# Analog_Master.net
KiCad netlist of a schematic drawn in EAGLE
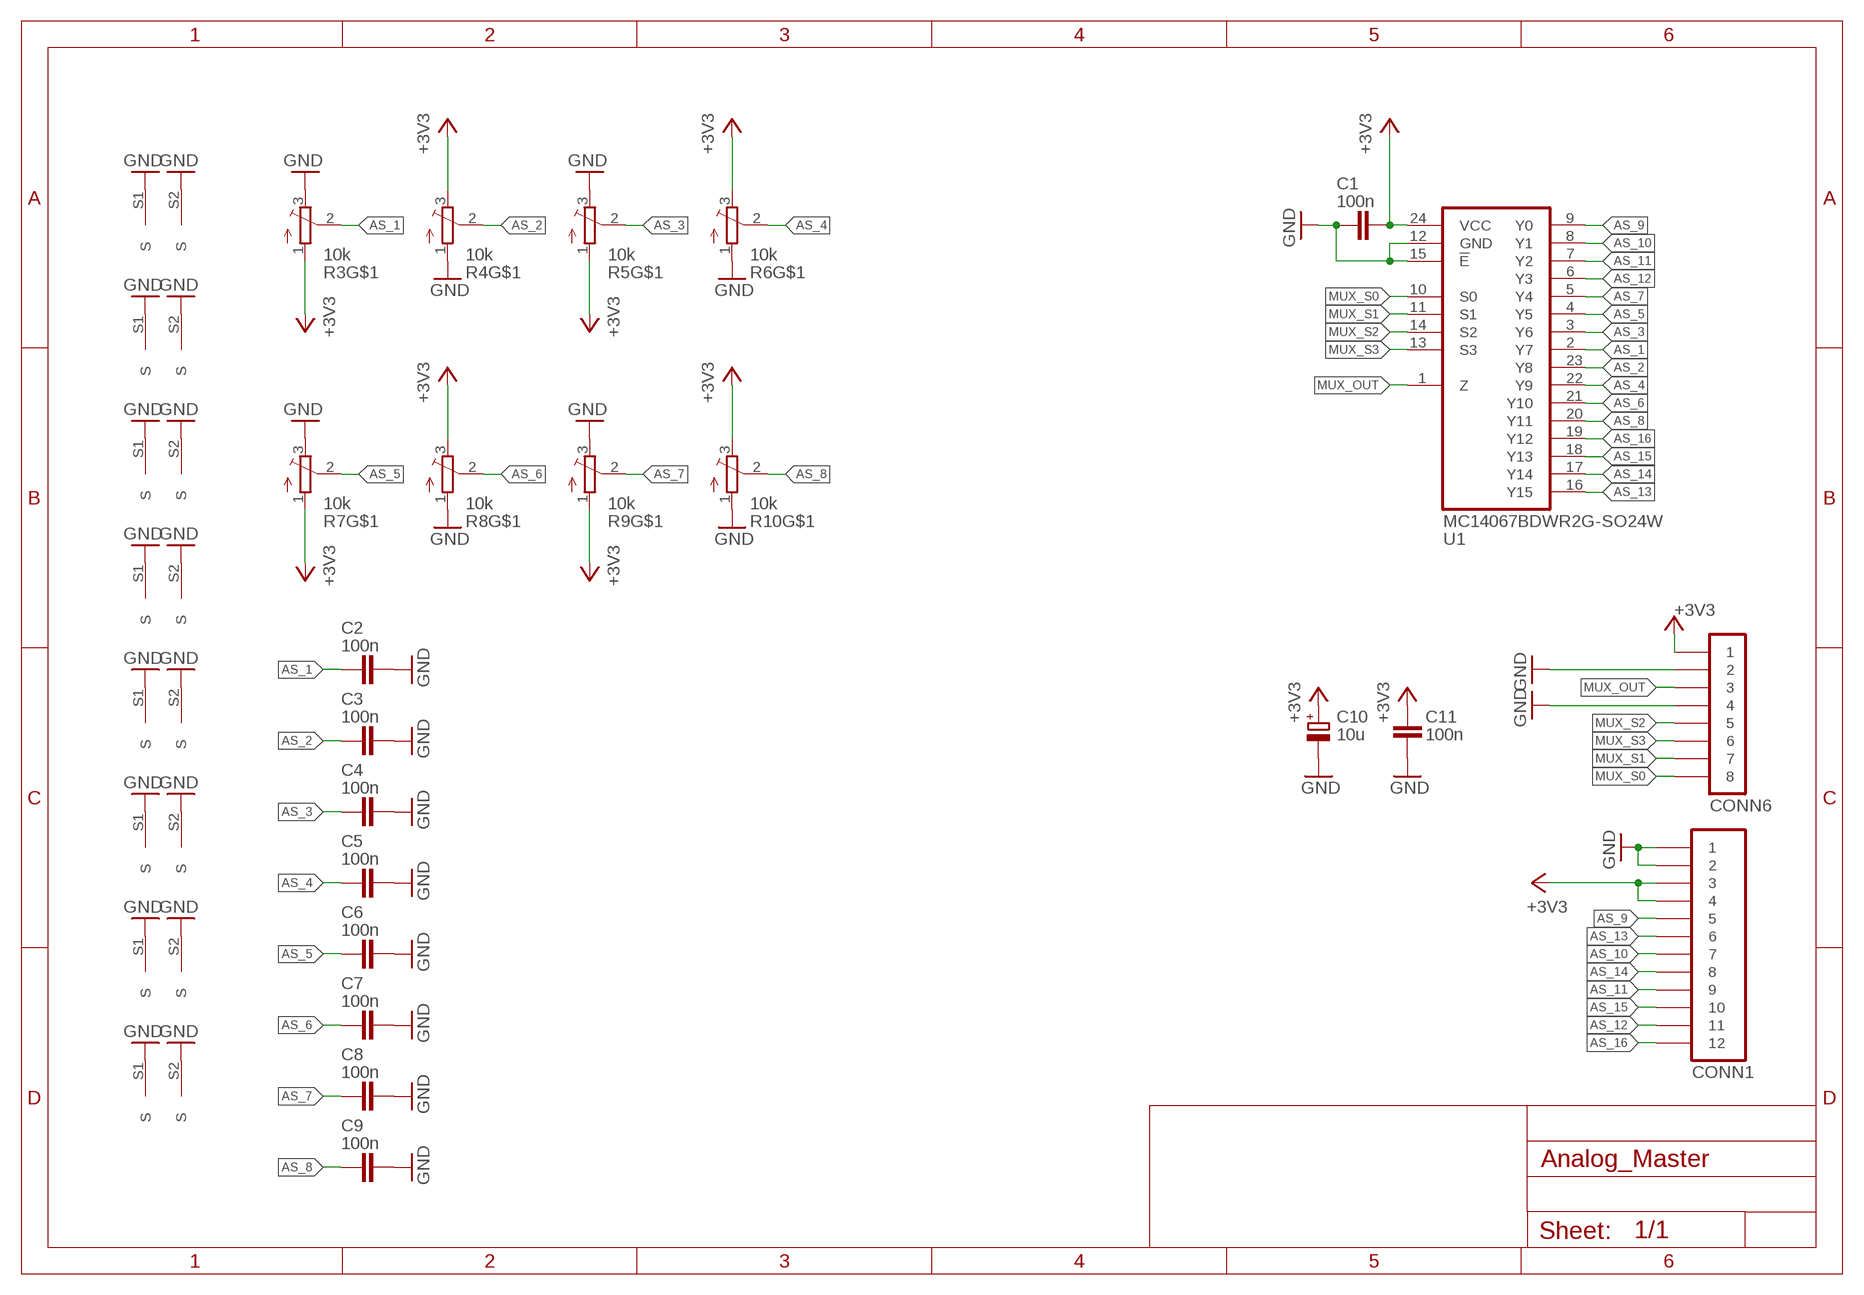
[diagram p0: schematic, sheet 1]

(export (version "E")
  (design (tool "Eeschema 10.0.6"))
  (components
    (comp (ref "C1")
      (value "100n")
      (footprint "eagle-import:C0805")
      (libsource (lib "eagle-import") (part "CAPACITOR-0805"))
    )
    (comp (ref "C2")
      (value "100n")
      (footprint "eagle-import:C0805")
      (libsource (lib "eagle-import") (part "CAPACITOR-0805"))
    )
    (comp (ref "C3")
      (value "100n")
      (footprint "eagle-import:C0805")
      (libsource (lib "eagle-import") (part "CAPACITOR-0805"))
    )
    (comp (ref "C4")
      (value "100n")
      (footprint "eagle-import:C0805")
      (libsource (lib "eagle-import") (part "CAPACITOR-0805"))
    )
    (comp (ref "C5")
      (value "100n")
      (footprint "eagle-import:C0805")
      (libsource (lib "eagle-import") (part "CAPACITOR-0805"))
    )
    (comp (ref "C6")
      (value "100n")
      (footprint "eagle-import:C0805")
      (libsource (lib "eagle-import") (part "CAPACITOR-0805"))
    )
    (comp (ref "C7")
      (value "100n")
      (footprint "eagle-import:C0805")
      (libsource (lib "eagle-import") (part "CAPACITOR-0805"))
    )
    (comp (ref "C8")
      (value "100n")
      (footprint "eagle-import:C0805")
      (libsource (lib "eagle-import") (part "CAPACITOR-0805"))
    )
    (comp (ref "C9")
      (value "100n")
      (footprint "eagle-import:C0805")
      (libsource (lib "eagle-import") (part "CAPACITOR-0805"))
    )
    (comp (ref "C10")
      (value "10u")
      (footprint "eagle-import:153CLV-0405")
      (fields (field (name "MANUFACTURER") "Multicomp") (field (name "MPN") "MCVVT016M100CA1L"))
      (libsource (lib "eagle-import") (part "ELECTROLYTIC_CAPACITOR-CLV-040516V"))
    )
    (comp (ref "C11")
      (value "100n")
      (footprint "eagle-import:C0805")
      (libsource (lib "eagle-import") (part "CAPACITOR-0805"))
    )
    (comp (ref "CONN1")
      (value "PINHD-2X06-IDC-2.54-V")
      (footprint "eagle-import:IDC-12P-2.54")
      (libsource (lib "eagle-import") (part "PINHD-2X06-IDC-2.54-V"))
    )
    (comp (ref "CONN6")
      (value "PINHD-2X04-IDC-2.54-V")
      (footprint "eagle-import:IDC-08P-2.54")
      (libsource (lib "eagle-import") (part "PINHD-2X04-IDC-2.54-V"))
    )
    (comp (ref "R3")
      (value "10k")
      (footprint "eagle-import:PTV09A-4025F-B103")
      (libsource (lib "eagle-import") (part "PTV09A-4025F-B103"))
    )
    (comp (ref "R4")
      (value "10k")
      (footprint "eagle-import:PTV09A-4025F-B103")
      (libsource (lib "eagle-import") (part "PTV09A-4025F-B103"))
    )
    (comp (ref "R5")
      (value "10k")
      (footprint "eagle-import:PTV09A-4025F-B103")
      (libsource (lib "eagle-import") (part "PTV09A-4025F-B103"))
    )
    (comp (ref "R6")
      (value "10k")
      (footprint "eagle-import:PTV09A-4025F-B103")
      (libsource (lib "eagle-import") (part "PTV09A-4025F-B103"))
    )
    (comp (ref "R7")
      (value "10k")
      (footprint "eagle-import:PTV09A-4025F-B103")
      (libsource (lib "eagle-import") (part "PTV09A-4025F-B103"))
    )
    (comp (ref "R8")
      (value "10k")
      (footprint "eagle-import:PTV09A-4025F-B103")
      (libsource (lib "eagle-import") (part "PTV09A-4025F-B103"))
    )
    (comp (ref "R9")
      (value "10k")
      (footprint "eagle-import:PTV09A-4025F-B103")
      (libsource (lib "eagle-import") (part "PTV09A-4025F-B103"))
    )
    (comp (ref "R10")
      (value "10k")
      (footprint "eagle-import:PTV09A-4025F-B103")
      (libsource (lib "eagle-import") (part "PTV09A-4025F-B103"))
    )
    (comp (ref "U1")
      (value "MC14067BDWR2G-SO24W")
      (footprint "eagle-import:SO24-W")
      (fields (field (name "MANUFACTURER") "ON Semiconductor") (field (name "MPN") "MC14067BDWR2G"))
      (libsource (lib "eagle-import") (part "MC14067BDWR2G-SO24W"))
    )
  )
  (nets
    (net (code "1") (name "+3V3") (class "Default")
      (node (ref "C1") (pin "2") (pinfunction "2_2") (pintype "passive"))
      (node (ref "C10") (pin "+") (pinfunction "+_+") (pintype "passive"))
      (node (ref "C11") (pin "1") (pinfunction "1_1") (pintype "passive"))
      (node (ref "CONN1") (pin "3") (pinfunction "3_3") (pintype "passive"))
      (node (ref "CONN1") (pin "4") (pinfunction "4_4") (pintype "passive"))
      (node (ref "CONN6") (pin "1") (pinfunction "1_1") (pintype "passive"))
      (node (ref "R10") (pin "3") (pinfunction "3_3") (pintype "passive"))
      (node (ref "R3") (pin "1") (pinfunction "1_1") (pintype "passive"))
      (node (ref "R4") (pin "3") (pinfunction "3_3") (pintype "passive"))
      (node (ref "R5") (pin "1") (pinfunction "1_1") (pintype "passive"))
      (node (ref "R6") (pin "3") (pinfunction "3_3") (pintype "passive"))
      (node (ref "R7") (pin "1") (pinfunction "1_1") (pintype "passive"))
      (node (ref "R8") (pin "3") (pinfunction "3_3") (pintype "passive"))
      (node (ref "R9") (pin "1") (pinfunction "1_1") (pintype "passive"))
      (node (ref "U1") (pin "24") (pinfunction "VCC_24") (pintype "passive"))
    )
    (net (code "2") (name "AS_1") (class "Default")
      (node (ref "C2") (pin "1") (pinfunction "1_1") (pintype "passive"))
      (node (ref "R3") (pin "2") (pinfunction "2_2") (pintype "passive"))
      (node (ref "U1") (pin "2") (pinfunction "Y7_2") (pintype "bidirectional"))
    )
    (net (code "3") (name "AS_2") (class "Default")
      (node (ref "C3") (pin "1") (pinfunction "1_1") (pintype "passive"))
      (node (ref "R4") (pin "2") (pinfunction "2_2") (pintype "passive"))
      (node (ref "U1") (pin "23") (pinfunction "Y8_23") (pintype "bidirectional"))
    )
    (net (code "4") (name "AS_3") (class "Default")
      (node (ref "C4") (pin "1") (pinfunction "1_1") (pintype "passive"))
      (node (ref "R5") (pin "2") (pinfunction "2_2") (pintype "passive"))
      (node (ref "U1") (pin "3") (pinfunction "Y6_3") (pintype "bidirectional"))
    )
    (net (code "5") (name "AS_4") (class "Default")
      (node (ref "C5") (pin "1") (pinfunction "1_1") (pintype "passive"))
      (node (ref "R6") (pin "2") (pinfunction "2_2") (pintype "passive"))
      (node (ref "U1") (pin "22") (pinfunction "Y9_22") (pintype "bidirectional"))
    )
    (net (code "6") (name "AS_5") (class "Default")
      (node (ref "C6") (pin "1") (pinfunction "1_1") (pintype "passive"))
      (node (ref "R7") (pin "2") (pinfunction "2_2") (pintype "passive"))
      (node (ref "U1") (pin "4") (pinfunction "Y5_4") (pintype "bidirectional"))
    )
    (net (code "7") (name "AS_6") (class "Default")
      (node (ref "C7") (pin "1") (pinfunction "1_1") (pintype "passive"))
      (node (ref "R8") (pin "2") (pinfunction "2_2") (pintype "passive"))
      (node (ref "U1") (pin "21") (pinfunction "Y10_21") (pintype "bidirectional"))
    )
    (net (code "8") (name "AS_7") (class "Default")
      (node (ref "C8") (pin "1") (pinfunction "1_1") (pintype "passive"))
      (node (ref "R9") (pin "2") (pinfunction "2_2") (pintype "passive"))
      (node (ref "U1") (pin "5") (pinfunction "Y4_5") (pintype "bidirectional"))
    )
    (net (code "9") (name "AS_8") (class "Default")
      (node (ref "C9") (pin "1") (pinfunction "1_1") (pintype "passive"))
      (node (ref "R10") (pin "2") (pinfunction "2_2") (pintype "passive"))
      (node (ref "U1") (pin "20") (pinfunction "Y11_20") (pintype "bidirectional"))
    )
    (net (code "10") (name "AS_9") (class "Default")
      (node (ref "CONN1") (pin "5") (pinfunction "5_5") (pintype "passive"))
      (node (ref "U1") (pin "9") (pinfunction "Y0_9") (pintype "bidirectional"))
    )
    (net (code "11") (name "AS_10") (class "Default")
      (node (ref "CONN1") (pin "7") (pinfunction "7_7") (pintype "passive"))
      (node (ref "U1") (pin "8") (pinfunction "Y1_8") (pintype "bidirectional"))
    )
    (net (code "12") (name "AS_11") (class "Default")
      (node (ref "CONN1") (pin "9") (pinfunction "9_9") (pintype "passive"))
      (node (ref "U1") (pin "7") (pinfunction "Y2_7") (pintype "bidirectional"))
    )
    (net (code "13") (name "AS_12") (class "Default")
      (node (ref "CONN1") (pin "11") (pinfunction "11_11") (pintype "passive"))
      (node (ref "U1") (pin "6") (pinfunction "Y3_6") (pintype "bidirectional"))
    )
    (net (code "14") (name "AS_13") (class "Default")
      (node (ref "CONN1") (pin "6") (pinfunction "6_6") (pintype "passive"))
      (node (ref "U1") (pin "16") (pinfunction "Y15_16") (pintype "bidirectional"))
    )
    (net (code "15") (name "AS_14") (class "Default")
      (node (ref "CONN1") (pin "8") (pinfunction "8_8") (pintype "passive"))
      (node (ref "U1") (pin "17") (pinfunction "Y14_17") (pintype "bidirectional"))
    )
    (net (code "16") (name "AS_15") (class "Default")
      (node (ref "CONN1") (pin "10") (pinfunction "10_10") (pintype "passive"))
      (node (ref "U1") (pin "18") (pinfunction "Y13_18") (pintype "bidirectional"))
    )
    (net (code "17") (name "AS_16") (class "Default")
      (node (ref "CONN1") (pin "12") (pinfunction "12_12") (pintype "passive"))
      (node (ref "U1") (pin "19") (pinfunction "Y12_19") (pintype "bidirectional"))
    )
    (net (code "18") (name "GND") (class "Default")
      (node (ref "C1") (pin "1") (pinfunction "1_1") (pintype "passive"))
      (node (ref "C10") (pin "-") (pinfunction "-_-") (pintype "passive"))
      (node (ref "C11") (pin "2") (pinfunction "2_2") (pintype "passive"))
      (node (ref "C2") (pin "2") (pinfunction "2_2") (pintype "passive"))
      (node (ref "C3") (pin "2") (pinfunction "2_2") (pintype "passive"))
      (node (ref "C4") (pin "2") (pinfunction "2_2") (pintype "passive"))
      (node (ref "C5") (pin "2") (pinfunction "2_2") (pintype "passive"))
      (node (ref "C6") (pin "2") (pinfunction "2_2") (pintype "passive"))
      (node (ref "C7") (pin "2") (pinfunction "2_2") (pintype "passive"))
      (node (ref "C8") (pin "2") (pinfunction "2_2") (pintype "passive"))
      (node (ref "C9") (pin "2") (pinfunction "2_2") (pintype "passive"))
      (node (ref "CONN1") (pin "1") (pinfunction "1_1") (pintype "passive"))
      (node (ref "CONN1") (pin "2") (pinfunction "2_2") (pintype "passive"))
      (node (ref "CONN6") (pin "2") (pinfunction "2_2") (pintype "passive"))
      (node (ref "CONN6") (pin "4") (pinfunction "4_4") (pintype "passive"))
      (node (ref "R10") (pin "1") (pinfunction "1_1") (pintype "passive"))
      (node (ref "R10") (pin "S1") (pinfunction "S_S1") (pintype "passive"))
      (node (ref "R10") (pin "S2") (pinfunction "S_S2") (pintype "passive"))
      (node (ref "R3") (pin "3") (pinfunction "3_3") (pintype "passive"))
      (node (ref "R3") (pin "S1") (pinfunction "S_S1") (pintype "passive"))
      (node (ref "R3") (pin "S2") (pinfunction "S_S2") (pintype "passive"))
      (node (ref "R4") (pin "1") (pinfunction "1_1") (pintype "passive"))
      (node (ref "R4") (pin "S1") (pinfunction "S_S1") (pintype "passive"))
      (node (ref "R4") (pin "S2") (pinfunction "S_S2") (pintype "passive"))
      (node (ref "R5") (pin "3") (pinfunction "3_3") (pintype "passive"))
      (node (ref "R5") (pin "S1") (pinfunction "S_S1") (pintype "passive"))
      (node (ref "R5") (pin "S2") (pinfunction "S_S2") (pintype "passive"))
      (node (ref "R6") (pin "1") (pinfunction "1_1") (pintype "passive"))
      (node (ref "R6") (pin "S1") (pinfunction "S_S1") (pintype "passive"))
      (node (ref "R6") (pin "S2") (pinfunction "S_S2") (pintype "passive"))
      (node (ref "R7") (pin "3") (pinfunction "3_3") (pintype "passive"))
      (node (ref "R7") (pin "S1") (pinfunction "S_S1") (pintype "passive"))
      (node (ref "R7") (pin "S2") (pinfunction "S_S2") (pintype "passive"))
      (node (ref "R8") (pin "1") (pinfunction "1_1") (pintype "passive"))
      (node (ref "R8") (pin "S1") (pinfunction "S_S1") (pintype "passive"))
      (node (ref "R8") (pin "S2") (pinfunction "S_S2") (pintype "passive"))
      (node (ref "R9") (pin "3") (pinfunction "3_3") (pintype "passive"))
      (node (ref "R9") (pin "S1") (pinfunction "S_S1") (pintype "passive"))
      (node (ref "R9") (pin "S2") (pinfunction "S_S2") (pintype "passive"))
      (node (ref "U1") (pin "12") (pinfunction "GND_12") (pintype "passive"))
      (node (ref "U1") (pin "15") (pinfunction "~{E}_15") (pintype "input"))
    )
    (net (code "19") (name "MUX_OUT") (class "Default")
      (node (ref "CONN6") (pin "3") (pinfunction "3_3") (pintype "passive"))
      (node (ref "U1") (pin "1") (pinfunction "Z_1") (pintype "bidirectional"))
    )
    (net (code "20") (name "MUX_S0") (class "Default")
      (node (ref "CONN6") (pin "8") (pinfunction "8_8") (pintype "passive"))
      (node (ref "U1") (pin "10") (pinfunction "S0_10") (pintype "input"))
    )
    (net (code "21") (name "MUX_S1") (class "Default")
      (node (ref "CONN6") (pin "7") (pinfunction "7_7") (pintype "passive"))
      (node (ref "U1") (pin "11") (pinfunction "S1_11") (pintype "input"))
    )
    (net (code "22") (name "MUX_S2") (class "Default")
      (node (ref "CONN6") (pin "5") (pinfunction "5_5") (pintype "passive"))
      (node (ref "U1") (pin "14") (pinfunction "S2_14") (pintype "input"))
    )
    (net (code "23") (name "MUX_S3") (class "Default")
      (node (ref "CONN6") (pin "6") (pinfunction "6_6") (pintype "passive"))
      (node (ref "U1") (pin "13") (pinfunction "S3_13") (pintype "input"))
    )
  )
)
